# 231006.net
KiCad netlist of a schematic drawn in Altium Designer
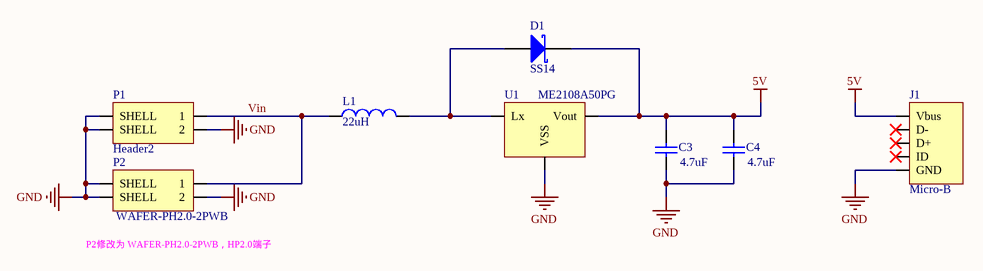
[diagram p0: 231006.SchDoc]

(export (version "E")
  (design (tool "Eeschema 10.0.6"))
  (components
    (comp (ref "C3")
      (value "4.7uF")
      (footprint "1206")
      (description "Capacitor")
      (fields (field (name "PUBLISHER") "Altium Limited"))
      (libsource (lib "Miscellaneous Devices") (part "Cap"))
    )
    (comp (ref "C4")
      (value "4.7uF")
      (footprint "1206")
      (description "Capacitor")
      (fields (field (name "PUBLISHER") "Altium Limited"))
      (libsource (lib "Miscellaneous Devices") (part "Cap"))
    )
    (comp (ref "D1")
      (value "SS14")
      (footprint "SOD_234")
      (description "Schottky Rectifier")
      (fields (field (name "PUBLISHER") "Altium Limited"))
      (libsource (lib "Miscellaneous Devices") (part "Diode 10TQ035"))
    )
    (comp (ref "J1") (value "Micro-B") (footprint "USB-MICRO_A") (libsource (lib "231006") (part "Micro-B")))
    (comp (ref "L1")
      (value "22uH")
      (footprint "231006:L_4.5X6")
      (description "Inductor")
      (fields (field (name "PUBLISHER") "Altium Limited"))
      (libsource (lib "Miscellaneous Devices") (part "Inductor"))
    )
    (comp (ref "P1") (value "Header2") (footprint "mh1.25-2P") (libsource (lib "231006") (part "Header2")))
    (comp (ref "P2")
      (value "WAFER-PH2.0-2PWB")
      (footprint "CONN-SMD_2P-P2.00_XUNPU_WAFER-PH2.0-2PWB")
      (libsource (lib "231006") (part "Header2"))
    )
    (comp (ref "U1")
      (value "ME2108A50PG")
      (footprint "SOT89")
      (libsource (lib "231006") (part "ME2108A50PG"))
    )
  )
  (nets
    (net (code "1") (name "/Vin") (class "Default")
      (node (ref "L1") (pin "1") (pinfunction "1_1") (pintype "passive"))
      (node (ref "P1") (pin "1") (pinfunction "1_1") (pintype "passive"))
      (node (ref "P2") (pin "1") (pinfunction "1_1") (pintype "passive"))
    )
    (net (code "2") (name "5V") (class "Default")
      (node (ref "C3") (pin "2") (pinfunction "2_2") (pintype "passive"))
      (node (ref "C4") (pin "2") (pinfunction "2_2") (pintype "passive"))
      (node (ref "D1") (pin "1") (pinfunction "K_1") (pintype "passive"))
      (node (ref "J1") (pin "1") (pinfunction "Vbus_1") (pintype "passive"))
      (node (ref "U1") (pin "2") (pinfunction "Vout_2") (pintype "passive"))
    )
    (net (code "3") (name "GND") (class "Default")
      (node (ref "C3") (pin "1") (pinfunction "1_1") (pintype "passive"))
      (node (ref "C4") (pin "1") (pinfunction "1_1") (pintype "passive"))
      (node (ref "J1") (pin "5") (pinfunction "GND_5") (pintype "passive"))
      (node (ref "P1") (pin "0") (pinfunction "SHELL_0") (pintype "passive"))
      (node (ref "P1") (pin "2") (pinfunction "2_2") (pintype "passive"))
      (node (ref "P2") (pin "0") (pinfunction "SHELL_0") (pintype "passive"))
      (node (ref "P2") (pin "2") (pinfunction "2_2") (pintype "passive"))
      (node (ref "U1") (pin "1") (pinfunction "VSS_1") (pintype "passive"))
    )
    (net (code "4") (name "Net-(D1-A)") (class "Default")
      (node (ref "D1") (pin "2") (pinfunction "A_2") (pintype "passive"))
      (node (ref "L1") (pin "2") (pinfunction "2_2") (pintype "passive"))
      (node (ref "U1") (pin "3") (pinfunction "Lx_3") (pintype "passive"))
    )
    (net (code "5") (name "unconnected-(J1-D+-Pad3)") (class "Default")
      (node (ref "J1") (pin "3") (pinfunction "D+_3") (pintype "passive+no_connect"))
    )
    (net (code "6") (name "unconnected-(J1-D--Pad2)") (class "Default")
      (node (ref "J1") (pin "2") (pinfunction "D-_2") (pintype "passive+no_connect"))
    )
    (net (code "7") (name "unconnected-(J1-ID-Pad4)") (class "Default")
      (node (ref "J1") (pin "4") (pinfunction "ID_4") (pintype "passive+no_connect"))
    )
  )
)
